# Sheet1_Lab08.net
KiCad netlist of a schematic drawn in Altium Designer
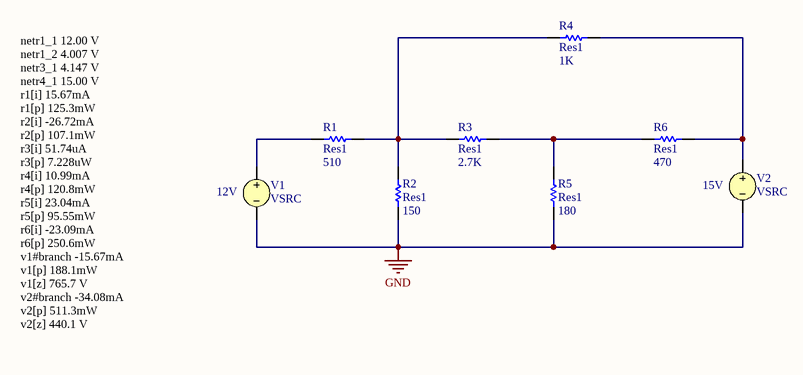
[diagram p0: Sheet1_Lab08.SchDoc]

(export (version "E")
  (design (tool "Eeschema 10.0.6"))
  (components
    (comp (ref "R1")
      (value "Res1")
      (footprint "AXIAL-0.3")
      (description "Resistor")
      (fields (field (name "ALTIUM_VALUE") "510") (field (name "PUBLISHER") "Altium Limited"))
      (libsource (lib "Miscellaneous Devices") (part "Res1"))
    )
    (comp (ref "R2")
      (value "Res1")
      (footprint "AXIAL-0.3")
      (description "Resistor")
      (fields (field (name "ALTIUM_VALUE") "150") (field (name "PUBLISHER") "Altium Limited"))
      (libsource (lib "Miscellaneous Devices") (part "Res1"))
    )
    (comp (ref "R3")
      (value "Res1")
      (footprint "AXIAL-0.3")
      (description "Resistor")
      (fields (field (name "ALTIUM_VALUE") "2.7K") (field (name "PUBLISHER") "Altium Limited"))
      (libsource (lib "Miscellaneous Devices") (part "Res1"))
    )
    (comp (ref "R4")
      (value "Res1")
      (footprint "AXIAL-0.3")
      (description "Resistor")
      (fields (field (name "ALTIUM_VALUE") "1K") (field (name "PUBLISHER") "Altium Limited"))
      (libsource (lib "Miscellaneous Devices") (part "Res1"))
    )
    (comp (ref "R5")
      (value "Res1")
      (footprint "AXIAL-0.3")
      (description "Resistor")
      (fields (field (name "ALTIUM_VALUE") "180") (field (name "PUBLISHER") "Altium Limited"))
      (libsource (lib "Miscellaneous Devices") (part "Res1"))
    )
    (comp (ref "R6")
      (value "Res1")
      (footprint "AXIAL-0.3")
      (description "Resistor")
      (fields (field (name "ALTIUM_VALUE") "470") (field (name "PUBLISHER") "Altium Limited"))
      (libsource (lib "Miscellaneous Devices") (part "Res1"))
    )
    (comp (ref "V1")
      (value "VSRC")
      (description "Voltage Source")
      (fields (field (name "ALTIUM_VALUE") "12V") (field (name "PUBLISHER") "Altium Limited"))
      (libsource (lib "Simulation Sources") (part "VSRC"))
    )
    (comp (ref "V2")
      (value "VSRC")
      (description "Voltage Source")
      (fields (field (name "ALTIUM_VALUE") "15V") (field (name "PUBLISHER") "Altium Limited"))
      (libsource (lib "Simulation Sources") (part "VSRC"))
    )
  )
  (nets
    (net (code "1") (name "GND") (class "Default")
      (node (ref "R2") (pin "1") (pinfunction "1_1") (pintype "passive"))
      (node (ref "R5") (pin "2") (pinfunction "2_2") (pintype "passive"))
      (node (ref "V1") (pin "2") (pinfunction "2_2") (pintype "passive"))
      (node (ref "V2") (pin "2") (pinfunction "2_2") (pintype "passive"))
    )
    (net (code "2") (name "Net-(R1-Pad1)") (class "Default")
      (node (ref "R1") (pin "1") (pinfunction "1_1") (pintype "passive"))
      (node (ref "V1") (pin "1") (pinfunction "1_1") (pintype "passive"))
    )
    (net (code "3") (name "Net-(R1-Pad2)") (class "Default")
      (node (ref "R1") (pin "2") (pinfunction "2_2") (pintype "passive"))
      (node (ref "R2") (pin "2") (pinfunction "2_2") (pintype "passive"))
      (node (ref "R3") (pin "2") (pinfunction "2_2") (pintype "passive"))
      (node (ref "R4") (pin "2") (pinfunction "2_2") (pintype "passive"))
    )
    (net (code "4") (name "Net-(R3-Pad1)") (class "Default")
      (node (ref "R3") (pin "1") (pinfunction "1_1") (pintype "passive"))
      (node (ref "R5") (pin "1") (pinfunction "1_1") (pintype "passive"))
      (node (ref "R6") (pin "1") (pinfunction "1_1") (pintype "passive"))
    )
    (net (code "5") (name "Net-(R4-Pad1)") (class "Default")
      (node (ref "R4") (pin "1") (pinfunction "1_1") (pintype "passive"))
      (node (ref "R6") (pin "2") (pinfunction "2_2") (pintype "passive"))
      (node (ref "V2") (pin "1") (pinfunction "1_1") (pintype "passive"))
    )
  )
)
